# atmega_TQFP32_to_DIP28.net
KiCad netlist of a schematic drawn in EAGLE
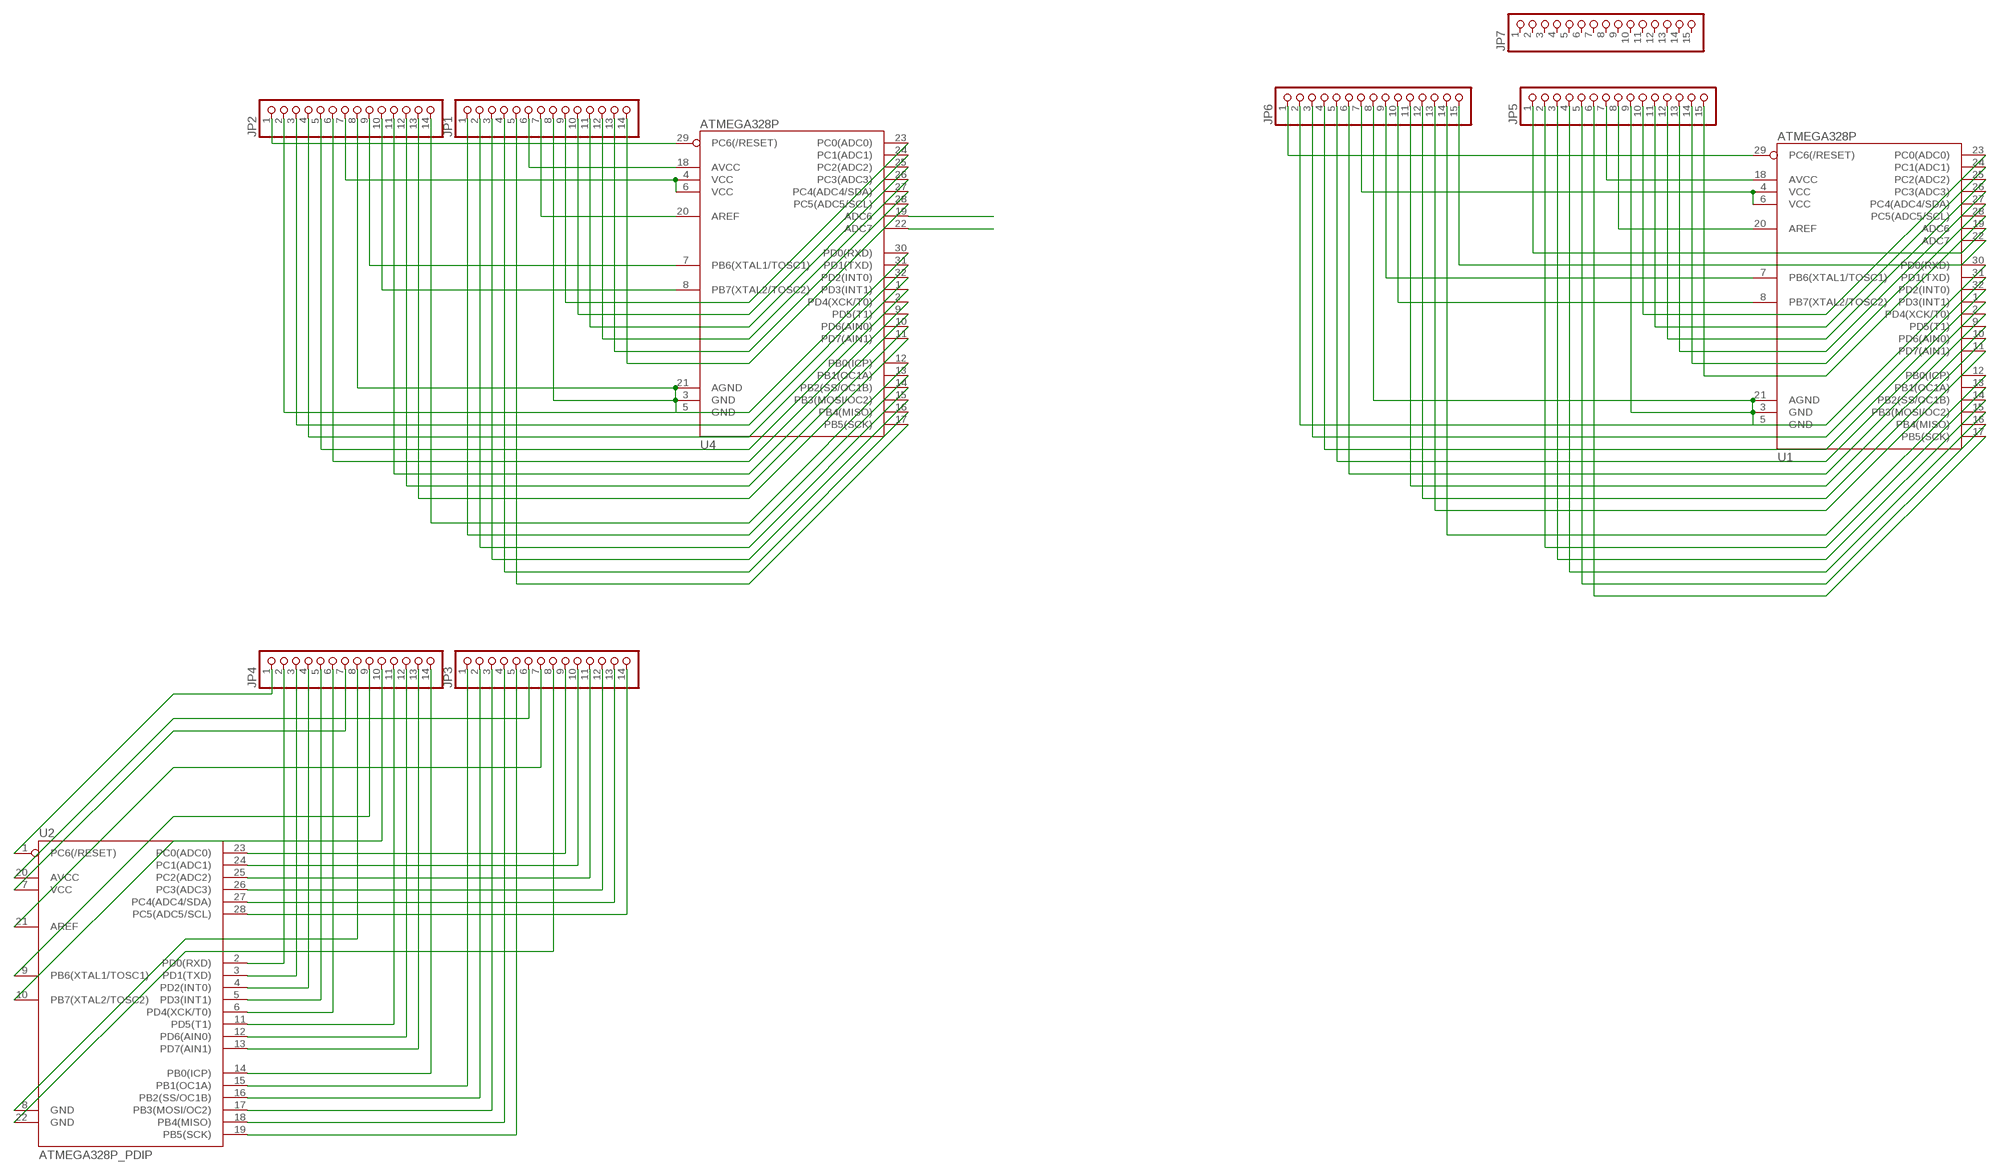
[diagram p0: schematic, sheet 1]

(export (version "E")
  (design (tool "Eeschema 10.0.6"))
  (components
    (comp (ref "JP1")
      (value "PINHD-1X14")
      (footprint "eagle-import:1X14")
      (libsource (lib "eagle-import") (part "PINHD-1X14"))
    )
    (comp (ref "JP2")
      (value "PINHD-1X14")
      (footprint "eagle-import:1X14")
      (libsource (lib "eagle-import") (part "PINHD-1X14"))
    )
    (comp (ref "JP3")
      (value "PINHD-1X14")
      (footprint "eagle-import:1X14")
      (libsource (lib "eagle-import") (part "PINHD-1X14"))
    )
    (comp (ref "JP4")
      (value "PINHD-1X14")
      (footprint "eagle-import:1X14")
      (libsource (lib "eagle-import") (part "PINHD-1X14"))
    )
    (comp (ref "JP5")
      (value "PINHD-1X15")
      (footprint "eagle-import:1X15")
      (libsource (lib "eagle-import") (part "PINHD-1X15"))
    )
    (comp (ref "JP6")
      (value "PINHD-1X15")
      (footprint "eagle-import:1X15")
      (libsource (lib "eagle-import") (part "PINHD-1X15"))
    )
    (comp (ref "JP7")
      (value "PINHD-1X15")
      (footprint "eagle-import:1X15")
      (libsource (lib "eagle-import") (part "PINHD-1X15"))
    )
    (comp (ref "U1")
      (value "ATMEGA328P")
      (footprint "eagle-import:TQFP32-08")
      (libsource (lib "eagle-import") (part "ATMEGA328_SMT"))
    )
    (comp (ref "U2")
      (value "ATMEGA328P_PDIP")
      (footprint "eagle-import:DIL28-3")
      (libsource (lib "eagle-import") (part "ATMEGA328P_PDIP"))
    )
    (comp (ref "U4")
      (value "ATMEGA328P")
      (footprint "eagle-import:TQFP32-08")
      (libsource (lib "eagle-import") (part "ATMEGA328_SMT"))
    )
  )
  (nets
    (net (code "1") (name "Net-(JP2-Pad7)") (class "Default")
      (node (ref "JP2") (pin "7") (pinfunction "7_7") (pintype "passive"))
      (node (ref "U4") (pin "4") (pinfunction "VCC_4") (pintype "bidirectional"))
      (node (ref "U4") (pin "6") (pinfunction "VCC_6") (pintype "bidirectional"))
    )
    (net (code "2") (name "Net-(JP3-Pad8)") (class "Default")
      (node (ref "JP3") (pin "8") (pinfunction "8_8") (pintype "passive"))
      (node (ref "U2") (pin "22") (pinfunction "GND_22") (pintype "bidirectional"))
    )
    (net (code "3") (name "Net-(JP4-Pad8)") (class "Default")
      (node (ref "JP4") (pin "8") (pinfunction "8_8") (pintype "passive"))
      (node (ref "U2") (pin "8") (pinfunction "GND_8") (pintype "bidirectional"))
    )
    (net (code "4") (name "Net-(JP6-Pad7)") (class "Default")
      (node (ref "JP6") (pin "7") (pinfunction "7_7") (pintype "passive"))
      (node (ref "U1") (pin "4") (pinfunction "VCC_4") (pintype "bidirectional"))
      (node (ref "U1") (pin "6") (pinfunction "VCC_6") (pintype "bidirectional"))
    )
    (net (code "5") (name "Net-(U1-ADC6)") (class "Default")
      (node (ref "JP5") (pin "1") (pinfunction "1_1") (pintype "passive"))
      (node (ref "U1") (pin "19") (pinfunction "ADC6_19") (pintype "bidirectional"))
    )
    (net (code "6") (name "Net-(U1-ADC7)") (class "Default")
      (node (ref "JP6") (pin "15") (pinfunction "15_15") (pintype "passive"))
      (node (ref "U1") (pin "22") (pinfunction "ADC7_22") (pintype "bidirectional"))
    )
    (net (code "7") (name "Net-(U1-AGND)") (class "Default")
      (node (ref "JP5") (pin "9") (pinfunction "9_9") (pintype "passive"))
      (node (ref "JP6") (pin "8") (pinfunction "8_8") (pintype "passive"))
      (node (ref "U1") (pin "21") (pinfunction "AGND_21") (pintype "bidirectional"))
      (node (ref "U1") (pin "3") (pinfunction "GND_3") (pintype "bidirectional"))
      (node (ref "U1") (pin "5") (pinfunction "GND_5") (pintype "bidirectional"))
    )
    (net (code "8") (name "Net-(U1-AREF)") (class "Default")
      (node (ref "JP5") (pin "8") (pinfunction "8_8") (pintype "passive"))
      (node (ref "U1") (pin "20") (pinfunction "AREF_20") (pintype "bidirectional"))
    )
    (net (code "9") (name "Net-(U1-AVCC)") (class "Default")
      (node (ref "JP5") (pin "7") (pinfunction "7_7") (pintype "passive"))
      (node (ref "U1") (pin "18") (pinfunction "AVCC_18") (pintype "bidirectional"))
    )
    (net (code "10") (name "Net-(U1-PB0(ICP))") (class "Default")
      (node (ref "JP6") (pin "14") (pinfunction "14_14") (pintype "passive"))
      (node (ref "U1") (pin "12") (pinfunction "PB0(ICP)_12") (pintype "bidirectional"))
    )
    (net (code "11") (name "Net-(U1-PB1(OC1A))") (class "Default")
      (node (ref "JP5") (pin "2") (pinfunction "2_2") (pintype "passive"))
      (node (ref "U1") (pin "13") (pinfunction "PB1(OC1A)_13") (pintype "bidirectional"))
    )
    (net (code "12") (name "Net-(U1-PB2(SS{slash}OC1B))") (class "Default")
      (node (ref "JP5") (pin "3") (pinfunction "3_3") (pintype "passive"))
      (node (ref "U1") (pin "14") (pinfunction "PB2(SS/OC1B)_14") (pintype "bidirectional"))
    )
    (net (code "13") (name "Net-(U1-PB3(MOSI{slash}OC2))") (class "Default")
      (node (ref "JP5") (pin "4") (pinfunction "4_4") (pintype "passive"))
      (node (ref "U1") (pin "15") (pinfunction "PB3(MOSI/OC2)_15") (pintype "bidirectional"))
    )
    (net (code "14") (name "Net-(U1-PB4(MISO))") (class "Default")
      (node (ref "JP5") (pin "5") (pinfunction "5_5") (pintype "passive"))
      (node (ref "U1") (pin "16") (pinfunction "PB4(MISO)_16") (pintype "bidirectional"))
    )
    (net (code "15") (name "Net-(U1-PB5(SCK))") (class "Default")
      (node (ref "JP5") (pin "6") (pinfunction "6_6") (pintype "passive"))
      (node (ref "U1") (pin "17") (pinfunction "PB5(SCK)_17") (pintype "bidirectional"))
    )
    (net (code "16") (name "Net-(U1-PB6(XTAL1{slash}TOSC1))") (class "Default")
      (node (ref "JP6") (pin "9") (pinfunction "9_9") (pintype "passive"))
      (node (ref "U1") (pin "7") (pinfunction "PB6(XTAL1/TOSC1)_7") (pintype "bidirectional"))
    )
    (net (code "17") (name "Net-(U1-PB7(XTAL2{slash}TOSC2))") (class "Default")
      (node (ref "JP6") (pin "10") (pinfunction "10_10") (pintype "passive"))
      (node (ref "U1") (pin "8") (pinfunction "PB7(XTAL2/TOSC2)_8") (pintype "bidirectional"))
    )
    (net (code "18") (name "Net-(U1-PC0(ADC0))") (class "Default")
      (node (ref "JP5") (pin "10") (pinfunction "10_10") (pintype "passive"))
      (node (ref "U1") (pin "23") (pinfunction "PC0(ADC0)_23") (pintype "bidirectional"))
    )
    (net (code "19") (name "Net-(U1-PC1(ADC1))") (class "Default")
      (node (ref "JP5") (pin "11") (pinfunction "11_11") (pintype "passive"))
      (node (ref "U1") (pin "24") (pinfunction "PC1(ADC1)_24") (pintype "bidirectional"))
    )
    (net (code "20") (name "Net-(U1-PC2(ADC2))") (class "Default")
      (node (ref "JP5") (pin "12") (pinfunction "12_12") (pintype "passive"))
      (node (ref "U1") (pin "25") (pinfunction "PC2(ADC2)_25") (pintype "bidirectional"))
    )
    (net (code "21") (name "Net-(U1-PC3(ADC3))") (class "Default")
      (node (ref "JP5") (pin "13") (pinfunction "13_13") (pintype "passive"))
      (node (ref "U1") (pin "26") (pinfunction "PC3(ADC3)_26") (pintype "bidirectional"))
    )
    (net (code "22") (name "Net-(U1-PC4(ADC4{slash}SDA))") (class "Default")
      (node (ref "JP5") (pin "14") (pinfunction "14_14") (pintype "passive"))
      (node (ref "U1") (pin "27") (pinfunction "PC4(ADC4/SDA)_27") (pintype "bidirectional"))
    )
    (net (code "23") (name "Net-(U1-PC5(ADC5{slash}SCL))") (class "Default")
      (node (ref "JP5") (pin "15") (pinfunction "15_15") (pintype "passive"))
      (node (ref "U1") (pin "28") (pinfunction "PC5(ADC5/SCL)_28") (pintype "bidirectional"))
    )
    (net (code "24") (name "Net-(U1-PC6({slash}RESET))") (class "Default")
      (node (ref "JP6") (pin "1") (pinfunction "1_1") (pintype "passive"))
      (node (ref "U1") (pin "29") (pinfunction "PC6(/RESET)_29") (pintype "bidirectional"))
    )
    (net (code "25") (name "Net-(U1-PD0(RXD))") (class "Default")
      (node (ref "JP6") (pin "2") (pinfunction "2_2") (pintype "passive"))
      (node (ref "U1") (pin "30") (pinfunction "PD0(RXD)_30") (pintype "bidirectional"))
    )
    (net (code "26") (name "Net-(U1-PD1(TXD))") (class "Default")
      (node (ref "JP6") (pin "3") (pinfunction "3_3") (pintype "passive"))
      (node (ref "U1") (pin "31") (pinfunction "PD1(TXD)_31") (pintype "bidirectional"))
    )
    (net (code "27") (name "Net-(U1-PD2(INT0))") (class "Default")
      (node (ref "JP6") (pin "4") (pinfunction "4_4") (pintype "passive"))
      (node (ref "U1") (pin "32") (pinfunction "PD2(INT0)_32") (pintype "bidirectional"))
    )
    (net (code "28") (name "Net-(U1-PD3(INT1))") (class "Default")
      (node (ref "JP6") (pin "5") (pinfunction "5_5") (pintype "passive"))
      (node (ref "U1") (pin "1") (pinfunction "PD3(INT1)_1") (pintype "bidirectional"))
    )
    (net (code "29") (name "Net-(U1-PD4(XCK{slash}T0))") (class "Default")
      (node (ref "JP6") (pin "6") (pinfunction "6_6") (pintype "passive"))
      (node (ref "U1") (pin "2") (pinfunction "PD4(XCK/T0)_2") (pintype "bidirectional"))
    )
    (net (code "30") (name "Net-(U1-PD5(T1))") (class "Default")
      (node (ref "JP6") (pin "11") (pinfunction "11_11") (pintype "passive"))
      (node (ref "U1") (pin "9") (pinfunction "PD5(T1)_9") (pintype "bidirectional"))
    )
    (net (code "31") (name "Net-(U1-PD6(AIN0))") (class "Default")
      (node (ref "JP6") (pin "12") (pinfunction "12_12") (pintype "passive"))
      (node (ref "U1") (pin "10") (pinfunction "PD6(AIN0)_10") (pintype "bidirectional"))
    )
    (net (code "32") (name "Net-(U1-PD7(AIN1))") (class "Default")
      (node (ref "JP6") (pin "13") (pinfunction "13_13") (pintype "passive"))
      (node (ref "U1") (pin "11") (pinfunction "PD7(AIN1)_11") (pintype "bidirectional"))
    )
    (net (code "33") (name "Net-(U2-AREF)") (class "Default")
      (node (ref "JP3") (pin "7") (pinfunction "7_7") (pintype "passive"))
      (node (ref "U2") (pin "21") (pinfunction "AREF_21") (pintype "bidirectional"))
    )
    (net (code "34") (name "Net-(U2-AVCC)") (class "Default")
      (node (ref "JP3") (pin "6") (pinfunction "6_6") (pintype "passive"))
      (node (ref "U2") (pin "20") (pinfunction "AVCC_20") (pintype "bidirectional"))
    )
    (net (code "35") (name "Net-(U2-PB0(ICP))") (class "Default")
      (node (ref "JP4") (pin "14") (pinfunction "14_14") (pintype "passive"))
      (node (ref "U2") (pin "14") (pinfunction "PB0(ICP)_14") (pintype "bidirectional"))
    )
    (net (code "36") (name "Net-(U2-PB1(OC1A))") (class "Default")
      (node (ref "JP3") (pin "1") (pinfunction "1_1") (pintype "passive"))
      (node (ref "U2") (pin "15") (pinfunction "PB1(OC1A)_15") (pintype "bidirectional"))
    )
    (net (code "37") (name "Net-(U2-PB2(SS{slash}OC1B))") (class "Default")
      (node (ref "JP3") (pin "2") (pinfunction "2_2") (pintype "passive"))
      (node (ref "U2") (pin "16") (pinfunction "PB2(SS/OC1B)_16") (pintype "bidirectional"))
    )
    (net (code "38") (name "Net-(U2-PB3(MOSI{slash}OC2))") (class "Default")
      (node (ref "JP3") (pin "3") (pinfunction "3_3") (pintype "passive"))
      (node (ref "U2") (pin "17") (pinfunction "PB3(MOSI/OC2)_17") (pintype "bidirectional"))
    )
    (net (code "39") (name "Net-(U2-PB4(MISO))") (class "Default")
      (node (ref "JP3") (pin "4") (pinfunction "4_4") (pintype "passive"))
      (node (ref "U2") (pin "18") (pinfunction "PB4(MISO)_18") (pintype "bidirectional"))
    )
    (net (code "40") (name "Net-(U2-PB5(SCK))") (class "Default")
      (node (ref "JP3") (pin "5") (pinfunction "5_5") (pintype "passive"))
      (node (ref "U2") (pin "19") (pinfunction "PB5(SCK)_19") (pintype "bidirectional"))
    )
    (net (code "41") (name "Net-(U2-PB6(XTAL1{slash}TOSC1))") (class "Default")
      (node (ref "JP4") (pin "9") (pinfunction "9_9") (pintype "passive"))
      (node (ref "U2") (pin "9") (pinfunction "PB6(XTAL1/TOSC1)_9") (pintype "bidirectional"))
    )
    (net (code "42") (name "Net-(U2-PB7(XTAL2{slash}TOSC2))") (class "Default")
      (node (ref "JP4") (pin "10") (pinfunction "10_10") (pintype "passive"))
      (node (ref "U2") (pin "10") (pinfunction "PB7(XTAL2/TOSC2)_10") (pintype "bidirectional"))
    )
    (net (code "43") (name "Net-(U2-PC0(ADC0))") (class "Default")
      (node (ref "JP3") (pin "9") (pinfunction "9_9") (pintype "passive"))
      (node (ref "U2") (pin "23") (pinfunction "PC0(ADC0)_23") (pintype "bidirectional"))
    )
    (net (code "44") (name "Net-(U2-PC1(ADC1))") (class "Default")
      (node (ref "JP3") (pin "10") (pinfunction "10_10") (pintype "passive"))
      (node (ref "U2") (pin "24") (pinfunction "PC1(ADC1)_24") (pintype "bidirectional"))
    )
    (net (code "45") (name "Net-(U2-PC2(ADC2))") (class "Default")
      (node (ref "JP3") (pin "11") (pinfunction "11_11") (pintype "passive"))
      (node (ref "U2") (pin "25") (pinfunction "PC2(ADC2)_25") (pintype "bidirectional"))
    )
    (net (code "46") (name "Net-(U2-PC3(ADC3))") (class "Default")
      (node (ref "JP3") (pin "12") (pinfunction "12_12") (pintype "passive"))
      (node (ref "U2") (pin "26") (pinfunction "PC3(ADC3)_26") (pintype "bidirectional"))
    )
    (net (code "47") (name "Net-(U2-PC4(ADC4{slash}SDA))") (class "Default")
      (node (ref "JP3") (pin "13") (pinfunction "13_13") (pintype "passive"))
      (node (ref "U2") (pin "27") (pinfunction "PC4(ADC4/SDA)_27") (pintype "bidirectional"))
    )
    (net (code "48") (name "Net-(U2-PC5(ADC5{slash}SCL))") (class "Default")
      (node (ref "JP3") (pin "14") (pinfunction "14_14") (pintype "passive"))
      (node (ref "U2") (pin "28") (pinfunction "PC5(ADC5/SCL)_28") (pintype "bidirectional"))
    )
    (net (code "49") (name "Net-(U2-PC6({slash}RESET))") (class "Default")
      (node (ref "JP4") (pin "1") (pinfunction "1_1") (pintype "passive"))
      (node (ref "U2") (pin "1") (pinfunction "PC6(/RESET)_1") (pintype "bidirectional"))
    )
    (net (code "50") (name "Net-(U2-PD0(RXD))") (class "Default")
      (node (ref "JP4") (pin "2") (pinfunction "2_2") (pintype "passive"))
      (node (ref "U2") (pin "2") (pinfunction "PD0(RXD)_2") (pintype "bidirectional"))
    )
    (net (code "51") (name "Net-(U2-PD1(TXD))") (class "Default")
      (node (ref "JP4") (pin "3") (pinfunction "3_3") (pintype "passive"))
      (node (ref "U2") (pin "3") (pinfunction "PD1(TXD)_3") (pintype "bidirectional"))
    )
    (net (code "52") (name "Net-(U2-PD2(INT0))") (class "Default")
      (node (ref "JP4") (pin "4") (pinfunction "4_4") (pintype "passive"))
      (node (ref "U2") (pin "4") (pinfunction "PD2(INT0)_4") (pintype "bidirectional"))
    )
    (net (code "53") (name "Net-(U2-PD3(INT1))") (class "Default")
      (node (ref "JP4") (pin "5") (pinfunction "5_5") (pintype "passive"))
      (node (ref "U2") (pin "5") (pinfunction "PD3(INT1)_5") (pintype "bidirectional"))
    )
    (net (code "54") (name "Net-(U2-PD4(XCK{slash}T0))") (class "Default")
      (node (ref "JP4") (pin "6") (pinfunction "6_6") (pintype "passive"))
      (node (ref "U2") (pin "6") (pinfunction "PD4(XCK/T0)_6") (pintype "bidirectional"))
    )
    (net (code "55") (name "Net-(U2-PD5(T1))") (class "Default")
      (node (ref "JP4") (pin "11") (pinfunction "11_11") (pintype "passive"))
      (node (ref "U2") (pin "11") (pinfunction "PD5(T1)_11") (pintype "bidirectional"))
    )
    (net (code "56") (name "Net-(U2-PD6(AIN0))") (class "Default")
      (node (ref "JP4") (pin "12") (pinfunction "12_12") (pintype "passive"))
      (node (ref "U2") (pin "12") (pinfunction "PD6(AIN0)_12") (pintype "bidirectional"))
    )
    (net (code "57") (name "Net-(U2-PD7(AIN1))") (class "Default")
      (node (ref "JP4") (pin "13") (pinfunction "13_13") (pintype "passive"))
      (node (ref "U2") (pin "13") (pinfunction "PD7(AIN1)_13") (pintype "bidirectional"))
    )
    (net (code "58") (name "Net-(U2-VCC)") (class "Default")
      (node (ref "JP4") (pin "7") (pinfunction "7_7") (pintype "passive"))
      (node (ref "U2") (pin "7") (pinfunction "VCC_7") (pintype "bidirectional"))
    )
    (net (code "59") (name "Net-(U4-AGND)") (class "Default")
      (node (ref "JP1") (pin "8") (pinfunction "8_8") (pintype "passive"))
      (node (ref "JP2") (pin "8") (pinfunction "8_8") (pintype "passive"))
      (node (ref "U4") (pin "21") (pinfunction "AGND_21") (pintype "bidirectional"))
      (node (ref "U4") (pin "3") (pinfunction "GND_3") (pintype "bidirectional"))
      (node (ref "U4") (pin "5") (pinfunction "GND_5") (pintype "bidirectional"))
    )
    (net (code "60") (name "Net-(U4-AREF)") (class "Default")
      (node (ref "JP1") (pin "7") (pinfunction "7_7") (pintype "passive"))
      (node (ref "U4") (pin "20") (pinfunction "AREF_20") (pintype "bidirectional"))
    )
    (net (code "61") (name "Net-(U4-AVCC)") (class "Default")
      (node (ref "JP1") (pin "6") (pinfunction "6_6") (pintype "passive"))
      (node (ref "U4") (pin "18") (pinfunction "AVCC_18") (pintype "bidirectional"))
    )
    (net (code "62") (name "Net-(U4-PB0(ICP))") (class "Default")
      (node (ref "JP2") (pin "14") (pinfunction "14_14") (pintype "passive"))
      (node (ref "U4") (pin "12") (pinfunction "PB0(ICP)_12") (pintype "bidirectional"))
    )
    (net (code "63") (name "Net-(U4-PB1(OC1A))") (class "Default")
      (node (ref "JP1") (pin "1") (pinfunction "1_1") (pintype "passive"))
      (node (ref "U4") (pin "13") (pinfunction "PB1(OC1A)_13") (pintype "bidirectional"))
    )
    (net (code "64") (name "Net-(U4-PB2(SS{slash}OC1B))") (class "Default")
      (node (ref "JP1") (pin "2") (pinfunction "2_2") (pintype "passive"))
      (node (ref "U4") (pin "14") (pinfunction "PB2(SS/OC1B)_14") (pintype "bidirectional"))
    )
    (net (code "65") (name "Net-(U4-PB3(MOSI{slash}OC2))") (class "Default")
      (node (ref "JP1") (pin "3") (pinfunction "3_3") (pintype "passive"))
      (node (ref "U4") (pin "15") (pinfunction "PB3(MOSI/OC2)_15") (pintype "bidirectional"))
    )
    (net (code "66") (name "Net-(U4-PB4(MISO))") (class "Default")
      (node (ref "JP1") (pin "4") (pinfunction "4_4") (pintype "passive"))
      (node (ref "U4") (pin "16") (pinfunction "PB4(MISO)_16") (pintype "bidirectional"))
    )
    (net (code "67") (name "Net-(U4-PB5(SCK))") (class "Default")
      (node (ref "JP1") (pin "5") (pinfunction "5_5") (pintype "passive"))
      (node (ref "U4") (pin "17") (pinfunction "PB5(SCK)_17") (pintype "bidirectional"))
    )
    (net (code "68") (name "Net-(U4-PB6(XTAL1{slash}TOSC1))") (class "Default")
      (node (ref "JP2") (pin "9") (pinfunction "9_9") (pintype "passive"))
      (node (ref "U4") (pin "7") (pinfunction "PB6(XTAL1/TOSC1)_7") (pintype "bidirectional"))
    )
    (net (code "69") (name "Net-(U4-PB7(XTAL2{slash}TOSC2))") (class "Default")
      (node (ref "JP2") (pin "10") (pinfunction "10_10") (pintype "passive"))
      (node (ref "U4") (pin "8") (pinfunction "PB7(XTAL2/TOSC2)_8") (pintype "bidirectional"))
    )
    (net (code "70") (name "Net-(U4-PC0(ADC0))") (class "Default")
      (node (ref "JP1") (pin "9") (pinfunction "9_9") (pintype "passive"))
      (node (ref "U4") (pin "23") (pinfunction "PC0(ADC0)_23") (pintype "bidirectional"))
    )
    (net (code "71") (name "Net-(U4-PC1(ADC1))") (class "Default")
      (node (ref "JP1") (pin "10") (pinfunction "10_10") (pintype "passive"))
      (node (ref "U4") (pin "24") (pinfunction "PC1(ADC1)_24") (pintype "bidirectional"))
    )
    (net (code "72") (name "Net-(U4-PC2(ADC2))") (class "Default")
      (node (ref "JP1") (pin "11") (pinfunction "11_11") (pintype "passive"))
      (node (ref "U4") (pin "25") (pinfunction "PC2(ADC2)_25") (pintype "bidirectional"))
    )
    (net (code "73") (name "Net-(U4-PC3(ADC3))") (class "Default")
      (node (ref "JP1") (pin "12") (pinfunction "12_12") (pintype "passive"))
      (node (ref "U4") (pin "26") (pinfunction "PC3(ADC3)_26") (pintype "bidirectional"))
    )
    (net (code "74") (name "Net-(U4-PC4(ADC4{slash}SDA))") (class "Default")
      (node (ref "JP1") (pin "13") (pinfunction "13_13") (pintype "passive"))
      (node (ref "U4") (pin "27") (pinfunction "PC4(ADC4/SDA)_27") (pintype "bidirectional"))
    )
    (net (code "75") (name "Net-(U4-PC5(ADC5{slash}SCL))") (class "Default")
      (node (ref "JP1") (pin "14") (pinfunction "14_14") (pintype "passive"))
      (node (ref "U4") (pin "28") (pinfunction "PC5(ADC5/SCL)_28") (pintype "bidirectional"))
    )
    (net (code "76") (name "Net-(U4-PC6({slash}RESET))") (class "Default")
      (node (ref "JP2") (pin "1") (pinfunction "1_1") (pintype "passive"))
      (node (ref "U4") (pin "29") (pinfunction "PC6(/RESET)_29") (pintype "bidirectional"))
    )
    (net (code "77") (name "Net-(U4-PD0(RXD))") (class "Default")
      (node (ref "JP2") (pin "2") (pinfunction "2_2") (pintype "passive"))
      (node (ref "U4") (pin "30") (pinfunction "PD0(RXD)_30") (pintype "bidirectional"))
    )
    (net (code "78") (name "Net-(U4-PD1(TXD))") (class "Default")
      (node (ref "JP2") (pin "3") (pinfunction "3_3") (pintype "passive"))
      (node (ref "U4") (pin "31") (pinfunction "PD1(TXD)_31") (pintype "bidirectional"))
    )
    (net (code "79") (name "Net-(U4-PD2(INT0))") (class "Default")
      (node (ref "JP2") (pin "4") (pinfunction "4_4") (pintype "passive"))
      (node (ref "U4") (pin "32") (pinfunction "PD2(INT0)_32") (pintype "bidirectional"))
    )
    (net (code "80") (name "Net-(U4-PD3(INT1))") (class "Default")
      (node (ref "JP2") (pin "5") (pinfunction "5_5") (pintype "passive"))
      (node (ref "U4") (pin "1") (pinfunction "PD3(INT1)_1") (pintype "bidirectional"))
    )
    (net (code "81") (name "Net-(U4-PD4(XCK{slash}T0))") (class "Default")
      (node (ref "JP2") (pin "6") (pinfunction "6_6") (pintype "passive"))
      (node (ref "U4") (pin "2") (pinfunction "PD4(XCK/T0)_2") (pintype "bidirectional"))
    )
    (net (code "82") (name "Net-(U4-PD5(T1))") (class "Default")
      (node (ref "JP2") (pin "11") (pinfunction "11_11") (pintype "passive"))
      (node (ref "U4") (pin "9") (pinfunction "PD5(T1)_9") (pintype "bidirectional"))
    )
    (net (code "83") (name "Net-(U4-PD6(AIN0))") (class "Default")
      (node (ref "JP2") (pin "12") (pinfunction "12_12") (pintype "passive"))
      (node (ref "U4") (pin "10") (pinfunction "PD6(AIN0)_10") (pintype "bidirectional"))
    )
    (net (code "84") (name "Net-(U4-PD7(AIN1))") (class "Default")
      (node (ref "JP2") (pin "13") (pinfunction "13_13") (pintype "passive"))
      (node (ref "U4") (pin "11") (pinfunction "PD7(AIN1)_11") (pintype "bidirectional"))
    )
    (net (code "85") (name "unconnected-(JP7-Pad1)") (class "Default")
      (node (ref "JP7") (pin "1") (pinfunction "1_1") (pintype "passive"))
    )
    (net (code "86") (name "unconnected-(JP7-Pad2)") (class "Default")
      (node (ref "JP7") (pin "2") (pinfunction "2_2") (pintype "passive"))
    )
    (net (code "87") (name "unconnected-(JP7-Pad3)") (class "Default")
      (node (ref "JP7") (pin "3") (pinfunction "3_3") (pintype "passive"))
    )
    (net (code "88") (name "unconnected-(JP7-Pad4)") (class "Default")
      (node (ref "JP7") (pin "4") (pinfunction "4_4") (pintype "passive"))
    )
    (net (code "89") (name "unconnected-(JP7-Pad5)") (class "Default")
      (node (ref "JP7") (pin "5") (pinfunction "5_5") (pintype "passive"))
    )
    (net (code "90") (name "unconnected-(JP7-Pad6)") (class "Default")
      (node (ref "JP7") (pin "6") (pinfunction "6_6") (pintype "passive"))
    )
    (net (code "91") (name "unconnected-(JP7-Pad7)") (class "Default")
      (node (ref "JP7") (pin "7") (pinfunction "7_7") (pintype "passive"))
    )
    (net (code "92") (name "unconnected-(JP7-Pad8)") (class "Default")
      (node (ref "JP7") (pin "8") (pinfunction "8_8") (pintype "passive"))
    )
    (net (code "93") (name "unconnected-(JP7-Pad9)") (class "Default")
      (node (ref "JP7") (pin "9") (pinfunction "9_9") (pintype "passive"))
    )
    (net (code "94") (name "unconnected-(JP7-Pad10)") (class "Default")
      (node (ref "JP7") (pin "10") (pinfunction "10_10") (pintype "passive"))
    )
    (net (code "95") (name "unconnected-(JP7-Pad11)") (class "Default")
      (node (ref "JP7") (pin "11") (pinfunction "11_11") (pintype "passive"))
    )
    (net (code "96") (name "unconnected-(JP7-Pad12)") (class "Default")
      (node (ref "JP7") (pin "12") (pinfunction "12_12") (pintype "passive"))
    )
    (net (code "97") (name "unconnected-(JP7-Pad13)") (class "Default")
      (node (ref "JP7") (pin "13") (pinfunction "13_13") (pintype "passive"))
    )
    (net (code "98") (name "unconnected-(JP7-Pad14)") (class "Default")
      (node (ref "JP7") (pin "14") (pinfunction "14_14") (pintype "passive"))
    )
    (net (code "99") (name "unconnected-(JP7-Pad15)") (class "Default")
      (node (ref "JP7") (pin "15") (pinfunction "15_15") (pintype "passive"))
    )
    (net (code "100") (name "unconnected-(U4-ADC6-Pad19)") (class "Default")
      (node (ref "U4") (pin "19") (pinfunction "ADC6_19") (pintype "bidirectional"))
    )
    (net (code "101") (name "unconnected-(U4-ADC7-Pad22)") (class "Default")
      (node (ref "U4") (pin "22") (pinfunction "ADC7_22") (pintype "bidirectional"))
    )
  )
)
